# ShieldBoard.net
KiCad netlist of a schematic drawn in Altium Designer
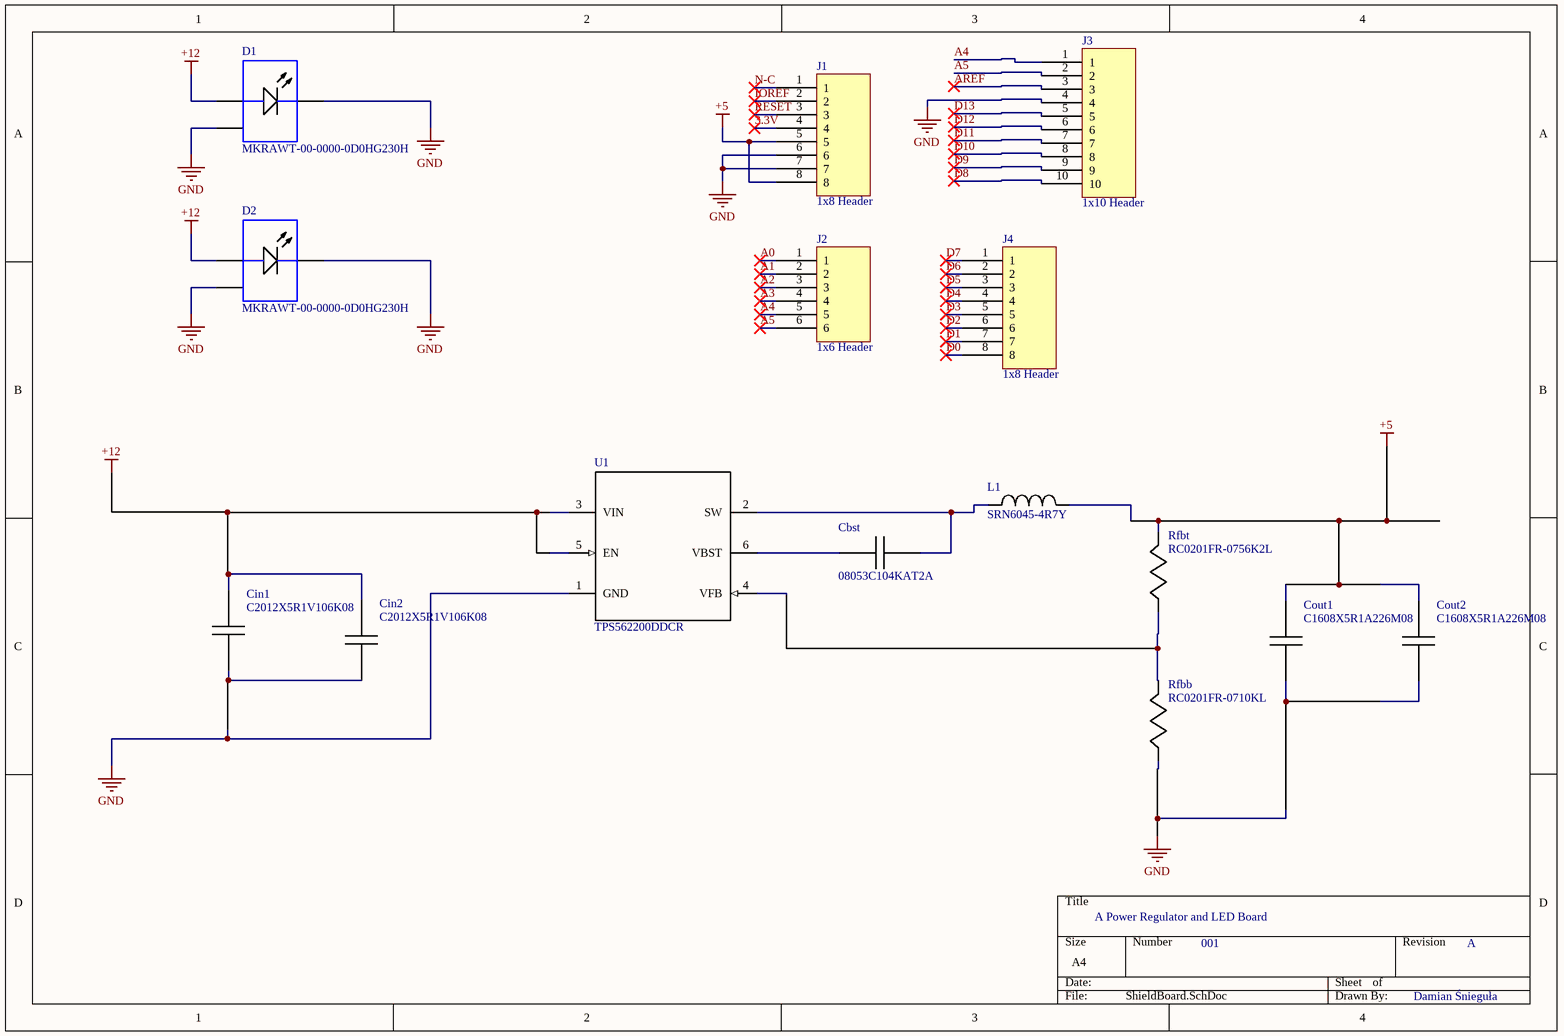
[diagram p0: ShieldBoard.SchDoc]

(export (version "E")
  (design (tool "Eeschema 10.0.6"))
  (components
    (comp (ref "Cbst")
      (value "08053C104KAT2A")
      (footprint "0805")
      (description "No Description Available")
      (fields (field (name "COPYRIGHT") "Copyright (C) 2018 Accelerated Designs. All rights reserved"))
      (libsource (lib "2022-11-13_14-23-18") (part "08053C104KAT2A"))
    )
    (comp (ref "Cin1")
      (value "C2012X5R1V106K08")
      (footprint "0805")
      (description "No Description Available")
      (fields
        (field (name "MANUFACTURER_PART_NUMBER") "C2012X5R1V106K085AC")
        (field (name "COPYRIGHT") "Copyright (C) 2018 Accelerated Designs. All rights reserved")
      )
      (libsource (lib "2022-11-13_14-23-18") (part "C2012X5R1V106K08"))
    )
    (comp (ref "Cin2")
      (value "C2012X5R1V106K08")
      (footprint "0805")
      (description "No Description Available")
      (fields
        (field (name "MANUFACTURER_PART_NUMBER") "C2012X5R1V106K085AC")
        (field (name "COPYRIGHT") "Copyright (C) 2018 Accelerated Designs. All rights reserved")
      )
      (libsource (lib "2022-11-13_14-23-18") (part "C2012X5R1V106K08"))
    )
    (comp (ref "Cout1")
      (value "C1608X5R1A226M08")
      (footprint "0603")
      (description "No Description Available")
      (fields
        (field (name "MANUFACTURER_PART_NUMBER") "C1608X5R1A226M080AC")
        (field (name "COPYRIGHT") "Copyright (C) 2018 Accelerated Designs. All rights reserved")
      )
      (libsource (lib "2022-11-13_14-23-18") (part "C1608X5R1A226M08"))
    )
    (comp (ref "Cout2")
      (value "C1608X5R1A226M08")
      (footprint "0603")
      (description "No Description Available")
      (fields
        (field (name "MANUFACTURER_PART_NUMBER") "C1608X5R1A226M080AC")
        (field (name "COPYRIGHT") "Copyright (C) 2018 Accelerated Designs. All rights reserved")
      )
      (libsource (lib "2022-11-13_14-23-18") (part "C1608X5R1A226M08"))
    )
    (comp (ref "D1")
      (value "MKRAWT-00-0000-0D0HG230H")
      (footprint "CREE-MK-R-2_V")
      (description "LED, White, 12 V, 2-Pin SMD, RoHS, Tape and Reel")
      (libsource (lib "Altium Content Vault") (part "LED_WHITE-3"))
    )
    (comp (ref "D2")
      (value "MKRAWT-00-0000-0D0HG230H")
      (footprint "CREE-MK-R-2_V")
      (description "LED, White, 12 V, 2-Pin SMD, RoHS, Tape and Reel")
      (libsource (lib "Altium Content Vault") (part "LED_WHITE-3"))
    )
    (comp (ref "J1")
      (value "1x8 Header")
      (footprint "PCBComponent_2")
      (fields (field (name "MANUFACTURER PART NUMBER") "SSQ-108-03-T-S"))
      (libsource (lib "PinHeader1x8") (part "8-Pin-Header"))
    )
    (comp (ref "J2")
      (value "1x6 Header")
      (footprint "PCBComponent_1")
      (fields (field (name "MANUFACTURER PART NUMBER") "SSQ-106-03-T-S"))
      (libsource (lib "PinHeader1x6") (part "6-Pin-Header"))
    )
    (comp (ref "J3")
      (value "1x10 Header")
      (footprint "PinHeader1x10:PCBComponent_3")
      (fields (field (name "MANUFACTURER PART NUMBER") "SSQ-110-03-T-S"))
      (libsource (lib "PinHeader1x10") (part "10-Pin-Header"))
    )
    (comp (ref "J4")
      (value "1x8 Header")
      (footprint "PCBComponent_2")
      (fields (field (name "MANUFACTURER PART NUMBER") "SSQ-108-03-T-S"))
      (libsource (lib "PinHeader1x8") (part "8-Pin-Header"))
    )
    (comp (ref "L1")
      (value "SRN6045-4R7Y")
      (footprint "SRN6045")
      (description "No Description Available")
      (fields (field (name "COPYRIGHT") "Copyright (C) 2018 Accelerated Designs. All rights reserved"))
      (libsource (lib "2022-11-13_14-23-18") (part "SRN6045-4R7Y"))
    )
    (comp (ref "Rfbb")
      (value "RC0201FR-0710KL")
      (footprint "0201")
      (description "No Description Available")
      (fields (field (name "COPYRIGHT") "Copyright (C) 2018 Accelerated Designs. All rights reserved"))
      (libsource (lib "2022-11-13_14-23-18") (part "RC0201FR-0710KL"))
    )
    (comp (ref "Rfbt")
      (value "RC0201FR-0756K2L")
      (footprint "0201")
      (description "No Description Available")
      (fields (field (name "COPYRIGHT") "Copyright (C) 2018 Accelerated Designs. All rights reserved"))
      (libsource (lib "2022-11-13_14-23-18") (part "RC0201FR-0756K2L"))
    )
    (comp (ref "U1")
      (value "TPS562200DDCR")
      (footprint "DDC0006A")
      (description "No Description Available")
      (fields
        (field (name "PARTNUMBER") "TPS562200DDC")
        (field (name "MANUFACTURER") "Texas Instruments")
        (field (name "MODIFIEDDATE") "Not shown in title block")
        (field (name "APPROVEDBY") "Not shown in title block")
        (field (name "CHECKEDBY") "Not shown in title block")
        (field (name "AUTHOR") "Not shown in title block")
        (field (name "ENGINEER") "Not shown in title block")
        (field (name "SYMBOLCREATOR") "a0411947")
        (field (name "PUBLISHER") "Texas Instruments")
        (field (name "COPYRIGHT") "Copyright (C) 2018 Accelerated Designs. All rights reserved")
      )
      (libsource (lib "2022-11-13_14-23-18") (part "TPS562200DDCR"))
    )
  )
  (nets
    (net (code "1") (name "+5") (class "Default")
      (node (ref "Cout1") (pin "1") (pinfunction "1_1") (pintype "passive"))
      (node (ref "Cout2") (pin "1") (pinfunction "1_1") (pintype "passive"))
      (node (ref "J1") (pin "5") (pinfunction "5_5") (pintype "passive"))
      (node (ref "J1") (pin "8") (pinfunction "8_8") (pintype "passive"))
      (node (ref "L1") (pin "2") (pinfunction "2_2") (pintype "passive"))
      (node (ref "Rfbt") (pin "1") (pinfunction "1_1") (pintype "passive"))
    )
    (net (code "2") (name "+12") (class "Default")
      (node (ref "Cin1") (pin "1") (pinfunction "1_1") (pintype "passive"))
      (node (ref "Cin2") (pin "1") (pinfunction "1_1") (pintype "passive"))
      (node (ref "D1") (pin "1") (pinfunction "A_1") (pintype "passive"))
      (node (ref "D2") (pin "1") (pinfunction "A_1") (pintype "passive"))
      (node (ref "U1") (pin "3") (pinfunction "VIN_3") (pintype "power_in"))
      (node (ref "U1") (pin "5") (pinfunction "EN_5") (pintype "input"))
    )
    (net (code "3") (name "/3.3V") (class "Default")
      (node (ref "J1") (pin "4") (pinfunction "4_4") (pintype "passive+no_connect"))
    )
    (net (code "4") (name "/A0") (class "Default")
      (node (ref "J2") (pin "1") (pinfunction "1_1") (pintype "passive+no_connect"))
    )
    (net (code "5") (name "/A1") (class "Default")
      (node (ref "J2") (pin "2") (pinfunction "2_2") (pintype "passive+no_connect"))
    )
    (net (code "6") (name "/A2") (class "Default")
      (node (ref "J2") (pin "3") (pinfunction "3_3") (pintype "passive+no_connect"))
    )
    (net (code "7") (name "/A3") (class "Default")
      (node (ref "J2") (pin "4") (pinfunction "4_4") (pintype "passive+no_connect"))
    )
    (net (code "8") (name "/A4") (class "Default")
      (node (ref "J2") (pin "5") (pinfunction "5_5") (pintype "passive"))
      (node (ref "J3") (pin "1") (pinfunction "1_1") (pintype "passive"))
    )
    (net (code "9") (name "/A5") (class "Default")
      (node (ref "J2") (pin "6") (pinfunction "6_6") (pintype "passive"))
      (node (ref "J3") (pin "2") (pinfunction "2_2") (pintype "passive"))
    )
    (net (code "10") (name "/AREF") (class "Default")
      (node (ref "J3") (pin "3") (pinfunction "3_3") (pintype "passive+no_connect"))
    )
    (net (code "11") (name "/D0") (class "Default")
      (node (ref "J4") (pin "8") (pinfunction "8_8") (pintype "passive+no_connect"))
    )
    (net (code "12") (name "/D1") (class "Default")
      (node (ref "J4") (pin "7") (pinfunction "7_7") (pintype "passive+no_connect"))
    )
    (net (code "13") (name "/D2") (class "Default")
      (node (ref "J4") (pin "6") (pinfunction "6_6") (pintype "passive+no_connect"))
    )
    (net (code "14") (name "/D3") (class "Default")
      (node (ref "J4") (pin "5") (pinfunction "5_5") (pintype "passive+no_connect"))
    )
    (net (code "15") (name "/D4") (class "Default")
      (node (ref "J4") (pin "4") (pinfunction "4_4") (pintype "passive+no_connect"))
    )
    (net (code "16") (name "/D5") (class "Default")
      (node (ref "J4") (pin "3") (pinfunction "3_3") (pintype "passive+no_connect"))
    )
    (net (code "17") (name "/D6") (class "Default")
      (node (ref "J4") (pin "2") (pinfunction "2_2") (pintype "passive+no_connect"))
    )
    (net (code "18") (name "/D7") (class "Default")
      (node (ref "J4") (pin "1") (pinfunction "1_1") (pintype "passive+no_connect"))
    )
    (net (code "19") (name "/D8") (class "Default")
      (node (ref "J3") (pin "10") (pinfunction "10_10") (pintype "passive+no_connect"))
    )
    (net (code "20") (name "/D9") (class "Default")
      (node (ref "J3") (pin "9") (pinfunction "9_9") (pintype "passive+no_connect"))
    )
    (net (code "21") (name "/D10") (class "Default")
      (node (ref "J3") (pin "8") (pinfunction "8_8") (pintype "passive+no_connect"))
    )
    (net (code "22") (name "/D11") (class "Default")
      (node (ref "J3") (pin "7") (pinfunction "7_7") (pintype "passive+no_connect"))
    )
    (net (code "23") (name "/D12") (class "Default")
      (node (ref "J3") (pin "6") (pinfunction "6_6") (pintype "passive+no_connect"))
    )
    (net (code "24") (name "/D13") (class "Default")
      (node (ref "J3") (pin "5") (pinfunction "5_5") (pintype "passive+no_connect"))
    )
    (net (code "25") (name "/IOREF") (class "Default")
      (node (ref "J1") (pin "2") (pinfunction "2_2") (pintype "passive+no_connect"))
    )
    (net (code "26") (name "/N-C") (class "Default")
      (node (ref "J1") (pin "1") (pinfunction "1_1") (pintype "passive+no_connect"))
    )
    (net (code "27") (name "/RESET") (class "Default")
      (node (ref "J1") (pin "3") (pinfunction "3_3") (pintype "passive+no_connect"))
    )
    (net (code "28") (name "GND") (class "Default")
      (node (ref "Cin1") (pin "2") (pinfunction "2_2") (pintype "passive"))
      (node (ref "Cin2") (pin "2") (pinfunction "2_2") (pintype "passive"))
      (node (ref "Cout1") (pin "2") (pinfunction "2_2") (pintype "passive"))
      (node (ref "Cout2") (pin "2") (pinfunction "2_2") (pintype "passive"))
      (node (ref "D1") (pin "2") (pinfunction "K_2") (pintype "passive"))
      (node (ref "D1") (pin "3") (pinfunction "EP_3") (pintype "passive"))
      (node (ref "D2") (pin "2") (pinfunction "K_2") (pintype "passive"))
      (node (ref "D2") (pin "3") (pinfunction "EP_3") (pintype "passive"))
      (node (ref "J1") (pin "6") (pinfunction "6_6") (pintype "passive"))
      (node (ref "J1") (pin "7") (pinfunction "7_7") (pintype "passive"))
      (node (ref "J3") (pin "4") (pinfunction "4_4") (pintype "passive"))
      (node (ref "Rfbb") (pin "2") (pinfunction "2_2") (pintype "passive"))
      (node (ref "U1") (pin "1") (pinfunction "GND_1") (pintype "power_in"))
    )
    (net (code "29") (name "Net-(U1-SW)") (class "Default")
      (node (ref "Cbst") (pin "1") (pinfunction "1_1") (pintype "passive"))
      (node (ref "L1") (pin "1") (pinfunction "1_1") (pintype "passive"))
      (node (ref "U1") (pin "2") (pinfunction "SW_2") (pintype "power_in"))
    )
    (net (code "30") (name "Net-(U1-VBST)") (class "Default")
      (node (ref "Cbst") (pin "2") (pinfunction "2_2") (pintype "passive"))
      (node (ref "U1") (pin "6") (pinfunction "VBST_6") (pintype "power_in"))
    )
    (net (code "31") (name "Net-(U1-VFB)") (class "Default")
      (node (ref "Rfbb") (pin "1") (pinfunction "1_1") (pintype "passive"))
      (node (ref "Rfbt") (pin "2") (pinfunction "2_2") (pintype "passive"))
      (node (ref "U1") (pin "4") (pinfunction "VFB_4") (pintype "input"))
    )
  )
)
